# DSO_Front.net
KiCad netlist of a schematic drawn in Altium Designer
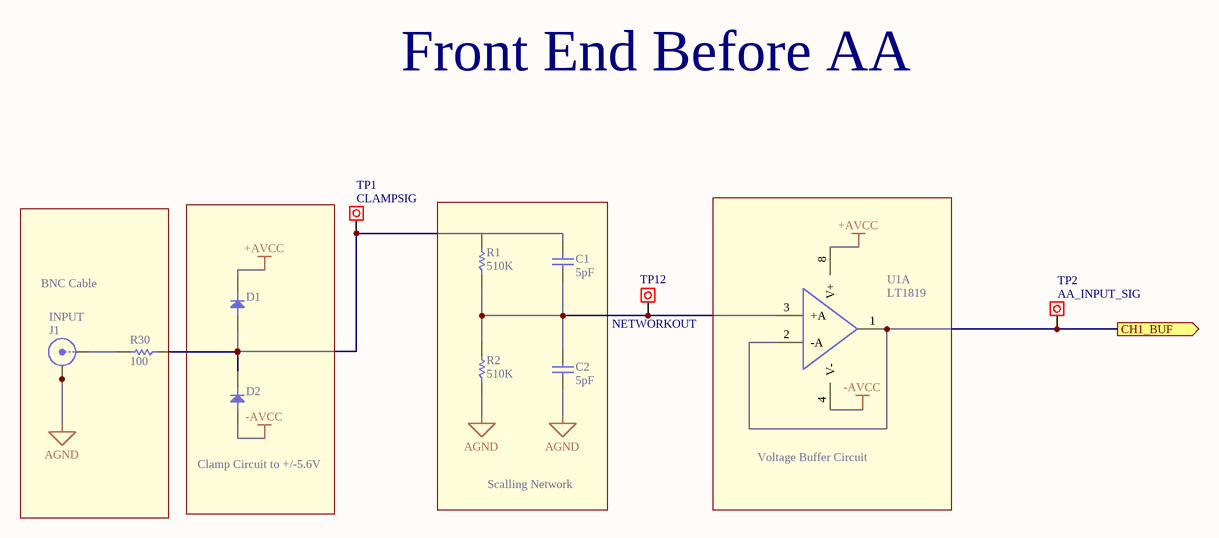
[diagram p0: DSO_Front.SchDoc]

(export (version "E")
  (design (tool "Eeschema 10.0.6"))
  (components
    (comp (ref "C1")
      (value "5pF")
      (footprint "0805C")
      (description "Capacitor")
      (fields (field (name "REVIEWED BY") "RM - 2018/08/05"))
      (libsource (lib "DSO") (part "C"))
    )
    (comp (ref "C2")
      (value "5pF")
      (footprint "0805C")
      (description "Capacitor")
      (fields (field (name "REVIEWED BY") "RM - 2018/08/05"))
      (libsource (lib "DSO") (part "C"))
    )
    (comp (ref "D1")
      (value "Diode")
      (footprint "SOD-123")
      (fields (field (name "REVIEWED BY") "RM - 2018/08/05"))
      (libsource (lib "DSO") (part "D"))
    )
    (comp (ref "D2")
      (value "Diode")
      (footprint "SOD-123")
      (fields (field (name "REVIEWED BY") "RM - 2018/08/05"))
      (libsource (lib "DSO") (part "D"))
    )
    (comp (ref "J1")
      (value "INPUT")
      (footprint "BNC_VERT")
      (description "BNC Straight")
      (fields (field (name "REVIEWED BY") "RM - 2018/08/05"))
      (libsource (lib "DSO") (part "BNC"))
    )
    (comp (ref "R1")
      (value "510K")
      (footprint "0805")
      (description "Resistor")
      (fields (field (name "REVIEWED BY") "RM - 2018/08/05"))
      (libsource (lib "DSO") (part "R"))
    )
    (comp (ref "R2")
      (value "510K")
      (footprint "0805")
      (description "Resistor")
      (fields (field (name "REVIEWED BY") "RM - 2018/08/05"))
      (libsource (lib "DSO") (part "R"))
    )
    (comp (ref "R30")
      (value "100")
      (footprint "0805")
      (description "Resistor")
      (fields (field (name "REVIEWED BY") "RM - 2018/08/05"))
      (libsource (lib "DSO") (part "R"))
    )
    (comp (ref "TP1")
      (value "CLAMPSIG")
      (footprint "Testpoin")
      (description "Pad")
      (fields (field (name "Comment") "INPUT"))
      (libsource (lib "DSO") (part "Test Point"))
    )
    (comp (ref "TP2")
      (value "AA_INPUT_SIG")
      (footprint "Testpoin")
      (description "Pad")
      (fields (field (name "Comment") "INPUT"))
      (libsource (lib "DSO") (part "Test Point"))
    )
    (comp (ref "TP12")
      (value "NETWORKOUT")
      (footprint "Testpoin")
      (description "Pad")
      (fields (field (name "Comment") "INPUT"))
      (libsource (lib "DSO") (part "Test Point"))
    )
    (comp (ref "U1")
      (value "LT1819")
      (footprint "SOIC-8")
      (description "OpAmp High Frequency Dual")
      (fields (field (name "REVIEWED BY") "RM - 2018/08/05"))
      (libsource (lib "DSO") (part "LT1819"))
    )
  )
  (nets
    (net (code "1") (name "+AVCC") (class "Default")
      (node (ref "D1") (pin "K") (pinfunction "K_K") (pintype "passive"))
      (node (ref "U1") (pin "8") (pinfunction "V+_8") (pintype "passive"))
    )
    (net (code "2") (name "-AVCC") (class "Default")
      (node (ref "D2") (pin "A") (pinfunction "A_A") (pintype "passive"))
      (node (ref "U1") (pin "4") (pinfunction "V-_4") (pintype "passive"))
    )
    (net (code "3") (name "/CH1_BUF") (class "Default")
      (node (ref "TP2") (pin "1") (pintype "passive"))
      (node (ref "U1") (pin "1") (pinfunction "OUTA_1") (pintype "passive"))
      (node (ref "U1") (pin "2") (pinfunction "-A_2") (pintype "passive"))
    )
    (net (code "4") (name "AGND") (class "Default")
      (node (ref "C2") (pin "2") (pinfunction "2_2") (pintype "passive"))
      (node (ref "J1") (pin "2") (pinfunction "Y_2") (pintype "passive"))
      (node (ref "J1") (pin "3") (pinfunction "Y_3") (pintype "passive"))
      (node (ref "J1") (pin "4") (pinfunction "Y_4") (pintype "passive"))
      (node (ref "J1") (pin "5") (pinfunction "Y_5") (pintype "passive"))
      (node (ref "R2") (pin "1") (pintype "passive"))
    )
    (net (code "5") (name "Net-(C1-Pad1)") (class "Default")
      (node (ref "C1") (pin "1") (pinfunction "1_1") (pintype "passive"))
      (node (ref "D1") (pin "A") (pinfunction "A_A") (pintype "passive"))
      (node (ref "D2") (pin "K") (pinfunction "K_K") (pintype "passive"))
      (node (ref "R30") (pin "1") (pintype "passive"))
      (node (ref "TP1") (pin "1") (pintype "passive"))
    )
    (net (code "6") (name "Net-(J1-X)") (class "Default")
      (node (ref "J1") (pin "1") (pinfunction "X_1") (pintype "passive"))
      (node (ref "R30") (pin "2") (pintype "passive"))
    )
    (net (code "7") (name "Net-(U1A-+A)") (class "Default")
      (node (ref "C1") (pin "2") (pinfunction "2_2") (pintype "passive"))
      (node (ref "C2") (pin "1") (pinfunction "1_1") (pintype "passive"))
      (node (ref "R1") (pin "1") (pintype "passive"))
      (node (ref "R2") (pin "2") (pintype "passive"))
      (node (ref "TP12") (pin "1") (pintype "passive"))
      (node (ref "U1") (pin "3") (pinfunction "+A_3") (pintype "passive"))
    )
    (net (code "8") (name "unconnected-(R1-Pad2)") (class "Default")
      (node (ref "R1") (pin "2") (pintype "passive"))
    )
  )
)
